# ps2_com_usb.net
KiCad netlist of a schematic drawn in EAGLE
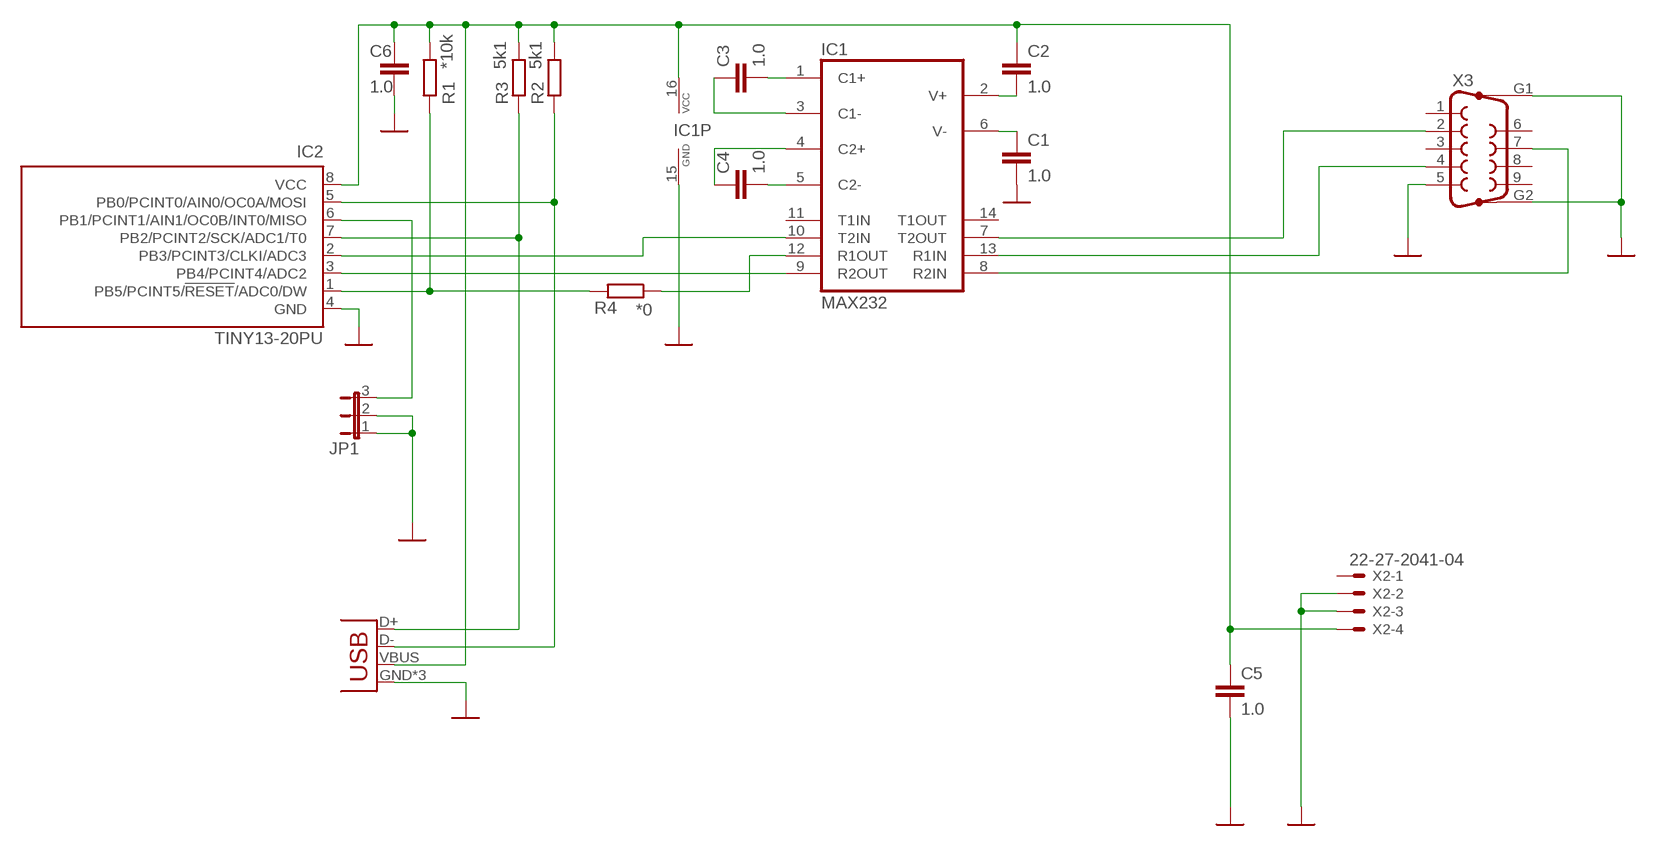
[diagram p0: schematic, sheet 1]

(export (version "E")
  (design (tool "Eeschema 10.0.6"))
  (components
    (comp (ref "C1")
      (value "1.0")
      (footprint "eagle-import:C025-025X050")
      (libsource (lib "eagle-import") (part "C-EU025-025X050"))
    )
    (comp (ref "C2")
      (value "1.0")
      (footprint "eagle-import:C025-025X050")
      (libsource (lib "eagle-import") (part "C-EU025-025X050"))
    )
    (comp (ref "C3")
      (value "1.0")
      (footprint "eagle-import:C025-025X050")
      (libsource (lib "eagle-import") (part "C-EU025-025X050"))
    )
    (comp (ref "C4")
      (value "1.0")
      (footprint "eagle-import:C025-025X050")
      (libsource (lib "eagle-import") (part "C-EU025-025X050"))
    )
    (comp (ref "C5")
      (value "1.0")
      (footprint "eagle-import:C025-025X050")
      (libsource (lib "eagle-import") (part "C-EU025-025X050"))
    )
    (comp (ref "C6")
      (value "1.0")
      (footprint "eagle-import:C025-025X050")
      (libsource (lib "eagle-import") (part "C-EU025-025X050"))
    )
    (comp (ref "IC1")
      (value "MAX232")
      (footprint "eagle-import:DIL16")
      (fields (field (name "MF") "MAXIM") (field (name "MPN") "MAX232ACPE+"))
      (libsource (lib "eagle-import") (part "MAX232"))
    )
    (comp (ref "IC2")
      (value "TINY13-20PU")
      (footprint "eagle-import:DIL08")
      (fields (field (name "MPN") "ATTINY13-20PU"))
      (libsource (lib "eagle-import") (part "TINY13PU-20"))
    )
    (comp (ref "JP1")
      (value "JP2E")
      (footprint "eagle-import:JP2")
      (libsource (lib "eagle-import") (part "JP2E"))
    )
    (comp (ref "R1")
      (value "*10k")
      (footprint "eagle-import:0204_7")
      (libsource (lib "eagle-import") (part "R-EU_0204/7"))
    )
    (comp (ref "R2")
      (value "5k1")
      (footprint "eagle-import:0204_5")
      (libsource (lib "eagle-import") (part "R-EU_0204/5"))
    )
    (comp (ref "R3")
      (value "5k1")
      (footprint "eagle-import:0204V")
      (libsource (lib "eagle-import") (part "R-EU_0204/2V"))
    )
    (comp (ref "R4")
      (value "*0")
      (footprint "eagle-import:0204V")
      (libsource (lib "eagle-import") (part "R-EU_0204/2V"))
    )
    (comp (ref "X1")
      (value "USB-A-H")
      (footprint "eagle-import:USB-A-H")
      (libsource (lib "eagle-import") (part "USB-A-H"))
    )
    (comp (ref "X2")
      (value "22-27-2041-04")
      (footprint "eagle-import:6410-04")
      (fields (field (name "MF") "MOLEX"))
      (libsource (lib "eagle-import") (part "22-?-0427-2041"))
    )
    (comp (ref "X3")
      (value "F09HP")
      (footprint "eagle-import:F09HP")
      (libsource (lib "eagle-import") (part "F09HP"))
    )
  )
  (nets
    (net (code "1") (name "GND") (class "Default")
      (node (ref "C1") (pin "2") (pinfunction "2_2") (pintype "passive"))
      (node (ref "C5") (pin "2") (pinfunction "2_2") (pintype "passive"))
      (node (ref "C6") (pin "2") (pinfunction "2_2") (pintype "passive"))
      (node (ref "IC1") (pin "15") (pinfunction "GND_15") (pintype "power_in"))
      (node (ref "IC2") (pin "4") (pinfunction "GND_4") (pintype "power_in"))
      (node (ref "JP1") (pin "1") (pinfunction "1_1") (pintype "passive"))
      (node (ref "JP1") (pin "2") (pinfunction "2_2") (pintype "passive"))
      (node (ref "X1") (pin "GND") (pinfunction "GND_GND") (pintype "bidirectional"))
      (node (ref "X1") (pin "P$5") (pinfunction "GND_P$5") (pintype "bidirectional"))
      (node (ref "X1") (pin "P$6") (pinfunction "GND_P$6") (pintype "bidirectional"))
      (node (ref "X2") (pin "2") (pinfunction "S_2") (pintype "passive"))
      (node (ref "X2") (pin "3") (pinfunction "S_3") (pintype "passive"))
      (node (ref "X3") (pin "5") (pinfunction "5_5") (pintype "passive"))
      (node (ref "X3") (pin "G1") (pinfunction "G1_G1") (pintype "passive"))
      (node (ref "X3") (pin "G2") (pinfunction "G2_G2") (pintype "passive"))
    )
    (net (code "2") (name "Net-(IC1A-C1+)") (class "Default")
      (node (ref "C3") (pin "2") (pinfunction "2_2") (pintype "passive"))
      (node (ref "IC1") (pin "1") (pinfunction "C1+_1") (pintype "bidirectional"))
    )
    (net (code "3") (name "Net-(IC1A-C1-)") (class "Default")
      (node (ref "C3") (pin "1") (pinfunction "1_1") (pintype "passive"))
      (node (ref "IC1") (pin "3") (pinfunction "C1-_3") (pintype "bidirectional"))
    )
    (net (code "4") (name "Net-(IC1A-C2+)") (class "Default")
      (node (ref "C4") (pin "1") (pinfunction "1_1") (pintype "passive"))
      (node (ref "IC1") (pin "4") (pinfunction "C2+_4") (pintype "bidirectional"))
    )
    (net (code "5") (name "Net-(IC1A-C2-)") (class "Default")
      (node (ref "C4") (pin "2") (pinfunction "2_2") (pintype "passive"))
      (node (ref "IC1") (pin "5") (pinfunction "C2-_5") (pintype "bidirectional"))
    )
    (net (code "6") (name "Net-(IC1A-R1IN)") (class "Default")
      (node (ref "IC1") (pin "13") (pinfunction "R1IN_13") (pintype "input"))
      (node (ref "X3") (pin "4") (pinfunction "4_4") (pintype "passive"))
    )
    (net (code "7") (name "Net-(IC1A-R1OUT)") (class "Default")
      (node (ref "IC1") (pin "12") (pinfunction "R1OUT_12") (pintype "output"))
      (node (ref "R4") (pin "1") (pinfunction "1_1") (pintype "passive"))
    )
    (net (code "8") (name "Net-(IC1A-R2IN)") (class "Default")
      (node (ref "IC1") (pin "8") (pinfunction "R2IN_8") (pintype "input"))
      (node (ref "X3") (pin "7") (pinfunction "7_7") (pintype "passive"))
    )
    (net (code "9") (name "Net-(IC1A-R2OUT)") (class "Default")
      (node (ref "IC1") (pin "9") (pinfunction "R2OUT_9") (pintype "output"))
      (node (ref "IC2") (pin "3") (pinfunction "PB4/PCINT4/ADC2_3") (pintype "bidirectional"))
    )
    (net (code "10") (name "Net-(IC1A-T2IN)") (class "Default")
      (node (ref "IC1") (pin "10") (pinfunction "T2IN_10") (pintype "input"))
      (node (ref "IC2") (pin "2") (pinfunction "PB3/PCINT3/CLKI/ADC3_2") (pintype "bidirectional"))
    )
    (net (code "11") (name "Net-(IC1A-T2OUT)") (class "Default")
      (node (ref "IC1") (pin "7") (pinfunction "T2OUT_7") (pintype "output"))
      (node (ref "X3") (pin "2") (pinfunction "2_2") (pintype "passive"))
    )
    (net (code "12") (name "Net-(IC1A-V+)") (class "Default")
      (node (ref "C2") (pin "2") (pinfunction "2_2") (pintype "passive"))
      (node (ref "IC1") (pin "2") (pinfunction "V+_2") (pintype "bidirectional"))
    )
    (net (code "13") (name "Net-(IC1A-V-)") (class "Default")
      (node (ref "C1") (pin "1") (pinfunction "1_1") (pintype "passive"))
      (node (ref "IC1") (pin "6") (pinfunction "V-_6") (pintype "bidirectional"))
    )
    (net (code "14") (name "Net-(IC1B-VCC)") (class "Default")
      (node (ref "C2") (pin "1") (pinfunction "1_1") (pintype "passive"))
      (node (ref "C5") (pin "1") (pinfunction "1_1") (pintype "passive"))
      (node (ref "C6") (pin "1") (pinfunction "1_1") (pintype "passive"))
      (node (ref "IC1") (pin "16") (pinfunction "VCC_16") (pintype "power_in"))
      (node (ref "IC2") (pin "8") (pinfunction "VCC_8") (pintype "power_in"))
      (node (ref "R1") (pin "2") (pinfunction "2_2") (pintype "passive"))
      (node (ref "R2") (pin "2") (pinfunction "2_2") (pintype "passive"))
      (node (ref "R3") (pin "2") (pinfunction "2_2") (pintype "passive"))
      (node (ref "X1") (pin "VBUS") (pinfunction "VBUS_VBUS") (pintype "bidirectional"))
      (node (ref "X2") (pin "4") (pinfunction "S_4") (pintype "passive"))
    )
    (net (code "15") (name "Net-(IC2-PB0{slash}PCINT0{slash}AIN0{slash}OC0A{slash}MOSI)") (class "Default")
      (node (ref "IC2") (pin "5") (pinfunction "PB0/PCINT0/AIN0/OC0A/MOSI_5") (pintype "bidirectional"))
      (node (ref "R2") (pin "1") (pinfunction "1_1") (pintype "passive"))
      (node (ref "X1") (pin "D-") (pinfunction "D-_D-") (pintype "bidirectional"))
    )
    (net (code "16") (name "Net-(IC2-PB1{slash}PCINT1{slash}AIN1{slash}OC0B{slash}INT0{slash}MISO)") (class "Default")
      (node (ref "IC2") (pin "6") (pinfunction "PB1/PCINT1/AIN1/OC0B/INT0/MISO_6") (pintype "bidirectional"))
      (node (ref "JP1") (pin "3") (pinfunction "3_3") (pintype "passive"))
    )
    (net (code "17") (name "Net-(IC2-PB2{slash}PCINT2{slash}SCK{slash}ADC1{slash}T0)") (class "Default")
      (node (ref "IC2") (pin "7") (pinfunction "PB2/PCINT2/SCK/ADC1/T0_7") (pintype "bidirectional"))
      (node (ref "R3") (pin "1") (pinfunction "1_1") (pintype "passive"))
      (node (ref "X1") (pin "D+") (pinfunction "D+_D+") (pintype "bidirectional"))
    )
    (net (code "18") (name "Net-(IC2-PB5{slash}PCINT5{slash}~{RESET}{slash}ADC0{slash}DW)") (class "Default")
      (node (ref "IC2") (pin "1") (pinfunction "PB5/PCINT5/~{RESET}/ADC0/DW_1") (pintype "bidirectional"))
      (node (ref "R1") (pin "1") (pinfunction "1_1") (pintype "passive"))
      (node (ref "R4") (pin "2") (pinfunction "2_2") (pintype "passive"))
    )
    (net (code "19") (name "unconnected-(IC1A-T1IN-Pad11)") (class "Default")
      (node (ref "IC1") (pin "11") (pinfunction "T1IN_11") (pintype "input"))
    )
    (net (code "20") (name "unconnected-(IC1A-T1OUT-Pad14)") (class "Default")
      (node (ref "IC1") (pin "14") (pinfunction "T1OUT_14") (pintype "output"))
    )
    (net (code "21") (name "unconnected-(X2A-S-Pad1)") (class "Default")
      (node (ref "X2") (pin "1") (pinfunction "S_1") (pintype "passive"))
    )
    (net (code "22") (name "unconnected-(X3-Pad1)") (class "Default")
      (node (ref "X3") (pin "1") (pinfunction "1_1") (pintype "passive"))
    )
    (net (code "23") (name "unconnected-(X3-Pad3)") (class "Default")
      (node (ref "X3") (pin "3") (pinfunction "3_3") (pintype "passive"))
    )
    (net (code "24") (name "unconnected-(X3-Pad6)") (class "Default")
      (node (ref "X3") (pin "6") (pinfunction "6_6") (pintype "passive"))
    )
    (net (code "25") (name "unconnected-(X3-Pad8)") (class "Default")
      (node (ref "X3") (pin "8") (pinfunction "8_8") (pintype "passive"))
    )
    (net (code "26") (name "unconnected-(X3-Pad9)") (class "Default")
      (node (ref "X3") (pin "9") (pinfunction "9_9") (pintype "passive"))
    )
  )
)
